# RADIO.net
KiCad netlist of a schematic drawn in EAGLE
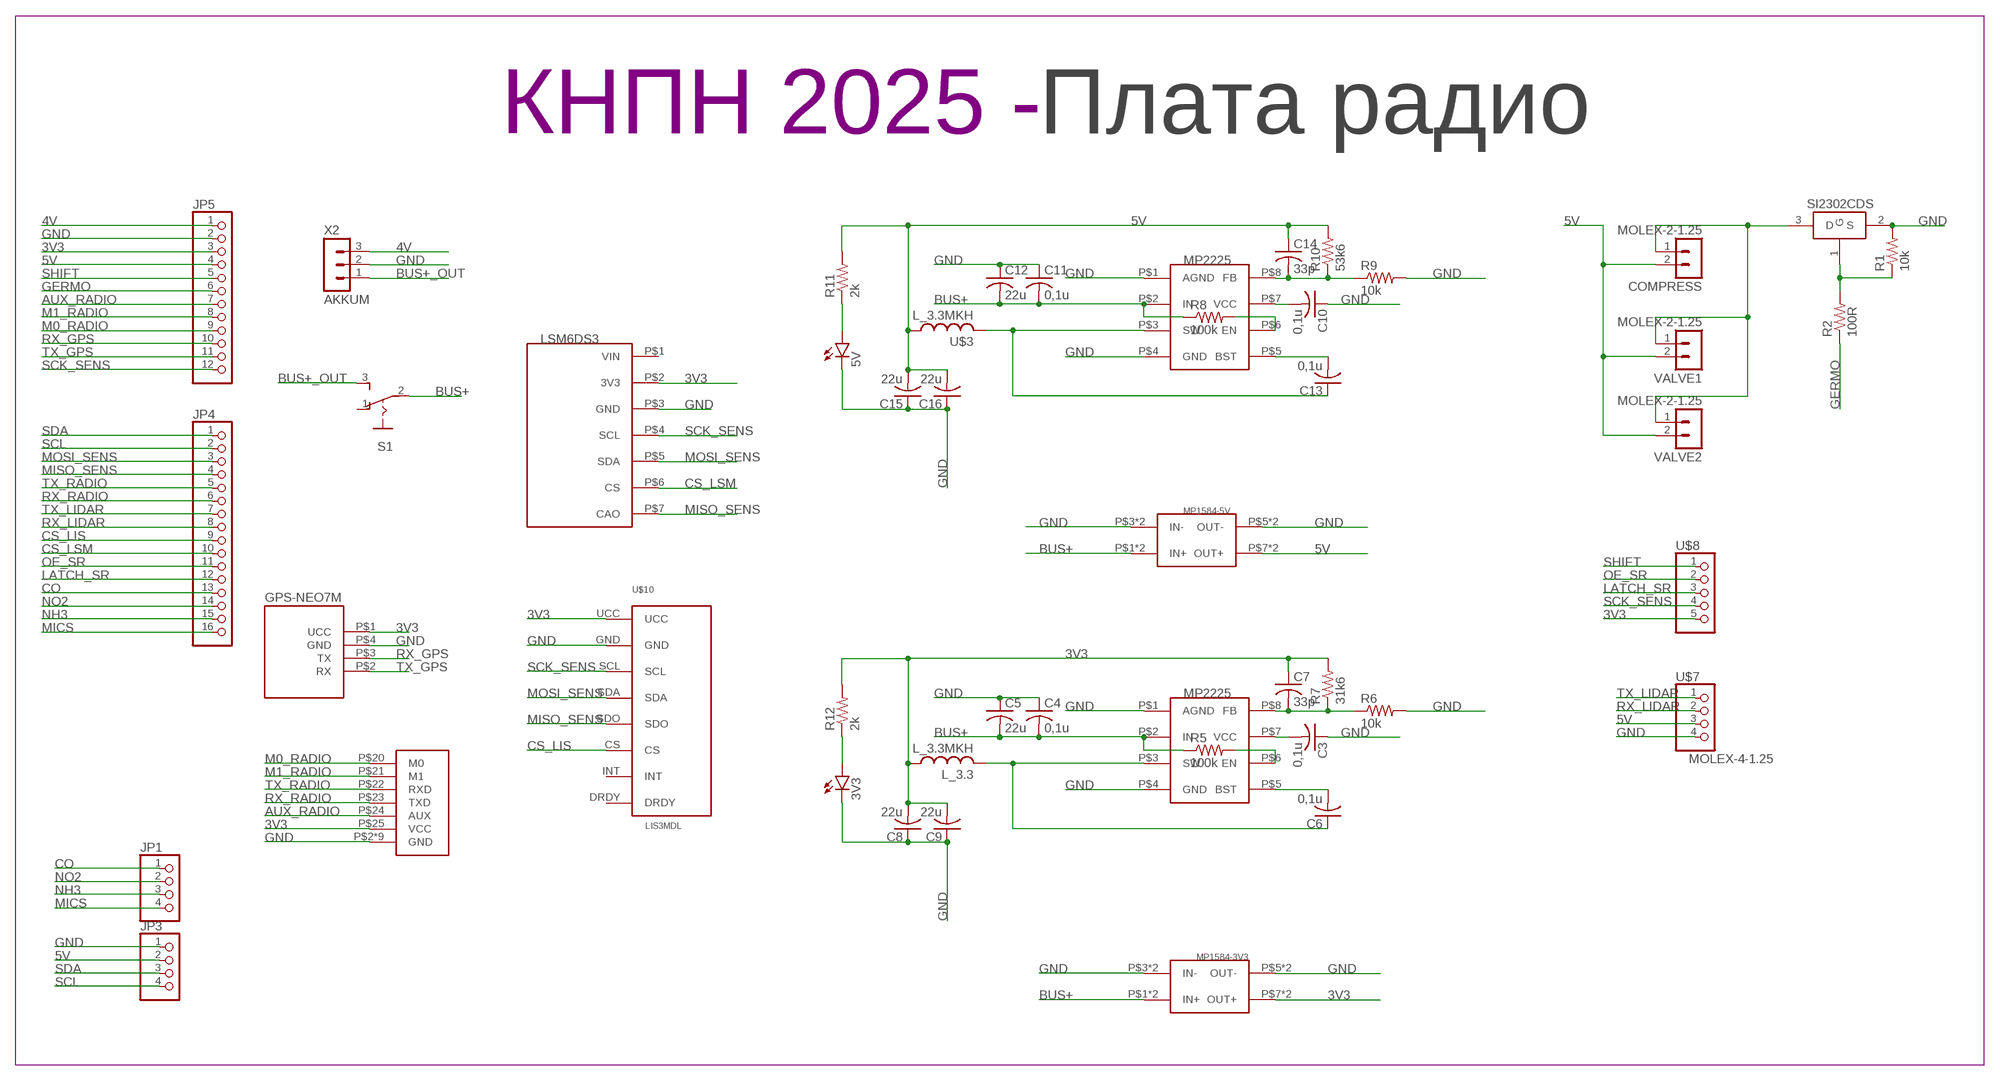
[diagram p0: schematic, sheet 1]

(export (version "E")
  (design (tool "Eeschema 10.0.6"))
  (components
    (comp (ref "3V3")
      (value "LEDCHIP-LED0603")
      (footprint "eagle-import:CHIP-LED0603")
      (libsource (lib "eagle-import") (part "LEDCHIP-LED0603"))
    )
    (comp (ref "5V")
      (value "LEDCHIP-LED0603")
      (footprint "eagle-import:CHIP-LED0603")
      (libsource (lib "eagle-import") (part "LEDCHIP-LED0603"))
    )
    (comp (ref "C3")
      (value "0,1u")
      (footprint "eagle-import:C0603")
      (libsource (lib "eagle-import") (part "C-USC0603"))
    )
    (comp (ref "C4")
      (value "0,1u")
      (footprint "eagle-import:C1206")
      (libsource (lib "eagle-import") (part "C-USC1206"))
    )
    (comp (ref "C5")
      (value "22u")
      (footprint "eagle-import:C0603")
      (libsource (lib "eagle-import") (part "C-USC0603"))
    )
    (comp (ref "C6")
      (value "0,1u")
      (footprint "eagle-import:C0603")
      (libsource (lib "eagle-import") (part "C-USC0603"))
    )
    (comp (ref "C7")
      (value "33p")
      (footprint "eagle-import:C0603")
      (libsource (lib "eagle-import") (part "C-USC0603"))
    )
    (comp (ref "C8")
      (value "22u")
      (footprint "eagle-import:C1206")
      (libsource (lib "eagle-import") (part "C-USC1206"))
    )
    (comp (ref "C9")
      (value "22u")
      (footprint "eagle-import:C1206")
      (libsource (lib "eagle-import") (part "C-USC1206"))
    )
    (comp (ref "C10")
      (value "0,1u")
      (footprint "eagle-import:C0603")
      (libsource (lib "eagle-import") (part "C-USC0603"))
    )
    (comp (ref "C11")
      (value "0,1u")
      (footprint "eagle-import:C1206")
      (libsource (lib "eagle-import") (part "C-USC1206"))
    )
    (comp (ref "C12")
      (value "22u")
      (footprint "eagle-import:C0603")
      (libsource (lib "eagle-import") (part "C-USC0603"))
    )
    (comp (ref "C13")
      (value "0,1u")
      (footprint "eagle-import:C0603")
      (libsource (lib "eagle-import") (part "C-USC0603"))
    )
    (comp (ref "C14")
      (value "33p")
      (footprint "eagle-import:C0603")
      (libsource (lib "eagle-import") (part "C-USC0603"))
    )
    (comp (ref "C15")
      (value "22u")
      (footprint "eagle-import:C1206")
      (libsource (lib "eagle-import") (part "C-USC1206"))
    )
    (comp (ref "C16")
      (value "22u")
      (footprint "eagle-import:C1206")
      (libsource (lib "eagle-import") (part "C-USC1206"))
    )
    (comp (ref "COMPRESS")
      (value "MOLEX-2-1.25")
      (footprint "eagle-import:53047-02")
      (libsource (lib "eagle-import") (part "MOLEX-2-1.25"))
    )
    (comp (ref "GPS-NEO7M")
      (value "GPS-NEO7M")
      (footprint "eagle-import:GPS-NEO7M")
      (libsource (lib "eagle-import") (part "GPS-NEO7M"))
    )
    (comp (ref "JP1")
      (value "PINHD-1X4")
      (footprint "eagle-import:1X04")
      (libsource (lib "eagle-import") (part "PINHD-1X4"))
    )
    (comp (ref "JP3")
      (value "PINHD-1X4")
      (footprint "eagle-import:1X04")
      (libsource (lib "eagle-import") (part "PINHD-1X4"))
    )
    (comp (ref "JP4")
      (value "PINHD-1X16")
      (footprint "eagle-import:1X16")
      (libsource (lib "eagle-import") (part "PINHD-1X16"))
    )
    (comp (ref "JP5")
      (value "PINHD-1X12")
      (footprint "eagle-import:1X12")
      (libsource (lib "eagle-import") (part "PINHD-1X12"))
    )
    (comp (ref "LSM6DS3")
      (value "LSM6DS3")
      (footprint "eagle-import:LSM6DS3_WITHOUT")
      (libsource (lib "eagle-import") (part "LSM6DS3_WITHOUT"))
    )
    (comp (ref "L_3.3")
      (value "L_3.3MKH")
      (footprint "eagle-import:L_SPM5020")
      (libsource (lib "eagle-import") (part "L_3.3MKH_5X5"))
    )
    (comp (ref "MP1584-3V3")
      (value "MP1584-B")
      (footprint "eagle-import:MP1584-B")
      (libsource (lib "eagle-import") (part "MP1584-B"))
    )
    (comp (ref "MP1584-5V")
      (value "MP1584")
      (footprint "eagle-import:MP1584-B")
      (libsource (lib "eagle-import") (part "MP1584-B"))
    )
    (comp (ref "R1")
      (value "10k")
      (footprint "eagle-import:R0603")
      (libsource (lib "eagle-import") (part "R-US_R0603"))
    )
    (comp (ref "R2")
      (value "100R")
      (footprint "eagle-import:R0603")
      (libsource (lib "eagle-import") (part "R-US_R0603"))
    )
    (comp (ref "R5")
      (value "100k")
      (footprint "eagle-import:R0603")
      (libsource (lib "eagle-import") (part "R-US_R0603"))
    )
    (comp (ref "R6")
      (value "10k")
      (footprint "eagle-import:R0603")
      (libsource (lib "eagle-import") (part "R-US_R0603"))
    )
    (comp (ref "R7")
      (value "31k6")
      (footprint "eagle-import:R0603")
      (libsource (lib "eagle-import") (part "R-US_R0603"))
    )
    (comp (ref "R8")
      (value "100k")
      (footprint "eagle-import:R0603")
      (libsource (lib "eagle-import") (part "R-US_R0603"))
    )
    (comp (ref "R9")
      (value "10k")
      (footprint "eagle-import:R0603")
      (libsource (lib "eagle-import") (part "R-US_R0603"))
    )
    (comp (ref "R10")
      (value "53k6")
      (footprint "eagle-import:R0603")
      (libsource (lib "eagle-import") (part "R-US_R0603"))
    )
    (comp (ref "R11")
      (value "2k")
      (footprint "eagle-import:R0603")
      (libsource (lib "eagle-import") (part "R-US_R0603"))
    )
    (comp (ref "R12")
      (value "2k")
      (footprint "eagle-import:R0603")
      (libsource (lib "eagle-import") (part "R-US_R0603"))
    )
    (comp (ref "RADIO")
      (value "E220-400T22S")
      (footprint "eagle-import:E220-400T22S")
      (libsource (lib "eagle-import") (part "E220-400T22S"))
    )
    (comp (ref "S1")
      (value "UNICS-SWITCHSS_12D11")
      (footprint "eagle-import:SS_12D11")
      (libsource (lib "eagle-import") (part "UNICS-SWITCHSS_12D11"))
    )
    (comp (ref "SI2302CDS")
      (value "SI2302CDS")
      (footprint "eagle-import:SOT23-3")
      (libsource (lib "eagle-import") (part "SI2302CDS"))
    )
    (comp (ref "U$1")
      (value "Плата радио")
      (footprint "eagle-import:LOGO")
      (libsource (lib "eagle-import") (part "LOGOPCB-{dblquote}{dblquote}"))
    )
    (comp (ref "U$2")
      (value "MP2225")
      (footprint "eagle-import:TSOT23-8")
      (libsource (lib "eagle-import") (part "MP2225"))
    )
    (comp (ref "U$3")
      (value "L_3.3MKH")
      (footprint "eagle-import:L_SPM5020")
      (libsource (lib "eagle-import") (part "L_3.3MKH_5X5"))
    )
    (comp (ref "U$5")
      (value "MP2225")
      (footprint "eagle-import:TSOT23-8")
      (libsource (lib "eagle-import") (part "MP2225"))
    )
    (comp (ref "U$7")
      (value "MOLEX-4-1.25")
      (footprint "eagle-import:53047-04")
      (libsource (lib "eagle-import") (part "MOLEX-4-1.25"))
    )
    (comp (ref "U$8")
      (value "MOLEX-5-1.25")
      (footprint "eagle-import:53047-05")
      (libsource (lib "eagle-import") (part "MOLEX-5-1.25"))
    )
    (comp (ref "U$10")
      (value "LIS3MDL")
      (footprint "eagle-import:LIS3MDL")
      (libsource (lib "eagle-import") (part "LIS3MDL"))
    )
    (comp (ref "VALVE1")
      (value "MOLEX-2-1.25")
      (footprint "eagle-import:53047-02")
      (libsource (lib "eagle-import") (part "MOLEX-2-1.25"))
    )
    (comp (ref "VALVE2")
      (value "MOLEX-2-1.25")
      (footprint "eagle-import:53047-02")
      (libsource (lib "eagle-import") (part "MOLEX-2-1.25"))
    )
    (comp (ref "X2")
      (value "AKKUM")
      (footprint "eagle-import:JST-3-2.5")
      (libsource (lib "eagle-import") (part "JST-3-2.5"))
    )
  )
  (nets
    (net (code "1") (name "/3V3") (class "Default")
      (node (ref "C7") (pin "1") (pinfunction "1_1") (pintype "passive"))
      (node (ref "C8") (pin "2") (pinfunction "2_2") (pintype "passive"))
      (node (ref "C9") (pin "2") (pinfunction "2_2") (pintype "passive"))
      (node (ref "GPS-NEO7M") (pin "P$1") (pinfunction "UCC_P$1") (pintype "bidirectional"))
      (node (ref "JP5") (pin "3") (pinfunction "3_3") (pintype "passive"))
      (node (ref "LSM6DS3") (pin "P$2") (pinfunction "3V3_P$2") (pintype "bidirectional"))
      (node (ref "L_3.3") (pin "P$1") (pinfunction "1_P$1") (pintype "passive"))
      (node (ref "MP1584-3V3") (pin "P$7") (pinfunction "OUT+_P$7") (pintype "bidirectional"))
      (node (ref "MP1584-3V3") (pin "P$8") (pinfunction "OUT+_P$8") (pintype "bidirectional"))
      (node (ref "R12") (pin "2") (pinfunction "2_2") (pintype "passive"))
      (node (ref "R7") (pin "2") (pinfunction "2_2") (pintype "passive"))
      (node (ref "RADIO") (pin "P$25") (pinfunction "VCC_P$25") (pintype "bidirectional"))
      (node (ref "U$10") (pin "UCC") (pinfunction "UCC_UCC") (pintype "bidirectional"))
      (node (ref "U$8") (pin "5") (pinfunction "5_5") (pintype "passive"))
    )
    (net (code "2") (name "/4V") (class "Default")
      (node (ref "JP5") (pin "1") (pinfunction "1_1") (pintype "passive"))
      (node (ref "X2") (pin "3") (pinfunction "3_3") (pintype "passive"))
    )
    (net (code "3") (name "/5V") (class "Default")
      (node (ref "C14") (pin "1") (pinfunction "1_1") (pintype "passive"))
      (node (ref "C15") (pin "2") (pinfunction "2_2") (pintype "passive"))
      (node (ref "C16") (pin "2") (pinfunction "2_2") (pintype "passive"))
      (node (ref "COMPRESS") (pin "2") (pinfunction "2_2") (pintype "passive"))
      (node (ref "JP3") (pin "2") (pinfunction "2_2") (pintype "passive"))
      (node (ref "JP5") (pin "4") (pinfunction "4_4") (pintype "passive"))
      (node (ref "MP1584-5V") (pin "P$7") (pinfunction "OUT+_P$7") (pintype "bidirectional"))
      (node (ref "MP1584-5V") (pin "P$8") (pinfunction "OUT+_P$8") (pintype "bidirectional"))
      (node (ref "R10") (pin "2") (pinfunction "2_2") (pintype "passive"))
      (node (ref "R11") (pin "2") (pinfunction "2_2") (pintype "passive"))
      (node (ref "U$3") (pin "P$1") (pinfunction "1_P$1") (pintype "passive"))
      (node (ref "U$7") (pin "3") (pinfunction "3_3") (pintype "passive"))
      (node (ref "VALVE1") (pin "2") (pinfunction "2_2") (pintype "passive"))
      (node (ref "VALVE2") (pin "2") (pinfunction "2_2") (pintype "passive"))
    )
    (net (code "4") (name "/AUX_RADIO") (class "Default")
      (node (ref "JP5") (pin "7") (pinfunction "7_7") (pintype "passive"))
      (node (ref "RADIO") (pin "P$24") (pinfunction "AUX_P$24") (pintype "bidirectional"))
    )
    (net (code "5") (name "/BUS+") (class "Default")
      (node (ref "C11") (pin "2") (pinfunction "2_2") (pintype "passive"))
      (node (ref "C12") (pin "2") (pinfunction "2_2") (pintype "passive"))
      (node (ref "C4") (pin "2") (pinfunction "2_2") (pintype "passive"))
      (node (ref "C5") (pin "2") (pinfunction "2_2") (pintype "passive"))
      (node (ref "MP1584-3V3") (pin "P$1") (pinfunction "IN+_P$1") (pintype "bidirectional"))
      (node (ref "MP1584-3V3") (pin "P$2") (pinfunction "IN+_P$2") (pintype "bidirectional"))
      (node (ref "MP1584-5V") (pin "P$1") (pinfunction "IN+_P$1") (pintype "bidirectional"))
      (node (ref "MP1584-5V") (pin "P$2") (pinfunction "IN+_P$2") (pintype "bidirectional"))
      (node (ref "R5") (pin "1") (pinfunction "1_1") (pintype "passive"))
      (node (ref "R8") (pin "1") (pinfunction "1_1") (pintype "passive"))
      (node (ref "S1") (pin "2") (pinfunction "P_2") (pintype "passive"))
      (node (ref "U$2") (pin "P$2") (pinfunction "IN_P$2") (pintype "bidirectional"))
      (node (ref "U$5") (pin "P$2") (pinfunction "IN_P$2") (pintype "bidirectional"))
    )
    (net (code "6") (name "/BUS+_OUT") (class "Default")
      (node (ref "S1") (pin "3") (pinfunction "S_3") (pintype "passive"))
      (node (ref "X2") (pin "1") (pinfunction "1_1") (pintype "passive"))
    )
    (net (code "7") (name "/CO") (class "Default")
      (node (ref "JP1") (pin "1") (pinfunction "1_1") (pintype "passive"))
      (node (ref "JP4") (pin "13") (pinfunction "13_13") (pintype "passive"))
    )
    (net (code "8") (name "/CS_LIS") (class "Default")
      (node (ref "JP4") (pin "9") (pinfunction "9_9") (pintype "passive"))
      (node (ref "U$10") (pin "CS") (pinfunction "CS_CS") (pintype "bidirectional"))
    )
    (net (code "9") (name "/CS_LSM") (class "Default")
      (node (ref "JP4") (pin "10") (pinfunction "10_10") (pintype "passive"))
      (node (ref "LSM6DS3") (pin "P$6") (pinfunction "CS_P$6") (pintype "bidirectional"))
    )
    (net (code "10") (name "/GERMO") (class "Default")
      (node (ref "JP5") (pin "6") (pinfunction "6_6") (pintype "passive"))
      (node (ref "R2") (pin "1") (pinfunction "1_1") (pintype "passive"))
    )
    (net (code "11") (name "/GND") (class "Default")
      (node (ref "3V3") (pin "C") (pinfunction "C_C") (pintype "passive"))
      (node (ref "5V") (pin "C") (pinfunction "C_C") (pintype "passive"))
      (node (ref "C10") (pin "1") (pinfunction "1_1") (pintype "passive"))
      (node (ref "C11") (pin "1") (pinfunction "1_1") (pintype "passive"))
      (node (ref "C12") (pin "1") (pinfunction "1_1") (pintype "passive"))
      (node (ref "C15") (pin "1") (pinfunction "1_1") (pintype "passive"))
      (node (ref "C16") (pin "1") (pinfunction "1_1") (pintype "passive"))
      (node (ref "C3") (pin "1") (pinfunction "1_1") (pintype "passive"))
      (node (ref "C4") (pin "1") (pinfunction "1_1") (pintype "passive"))
      (node (ref "C5") (pin "1") (pinfunction "1_1") (pintype "passive"))
      (node (ref "C8") (pin "1") (pinfunction "1_1") (pintype "passive"))
      (node (ref "C9") (pin "1") (pinfunction "1_1") (pintype "passive"))
      (node (ref "GPS-NEO7M") (pin "P$4") (pinfunction "GND_P$4") (pintype "bidirectional"))
      (node (ref "JP3") (pin "1") (pinfunction "1_1") (pintype "passive"))
      (node (ref "JP5") (pin "2") (pinfunction "2_2") (pintype "passive"))
      (node (ref "LSM6DS3") (pin "P$3") (pinfunction "GND_P$3") (pintype "bidirectional"))
      (node (ref "MP1584-3V3") (pin "P$3") (pinfunction "IN-_P$3") (pintype "bidirectional"))
      (node (ref "MP1584-3V3") (pin "P$4") (pinfunction "IN-_P$4") (pintype "bidirectional"))
      (node (ref "MP1584-3V3") (pin "P$5") (pinfunction "OUT-_P$5") (pintype "bidirectional"))
      (node (ref "MP1584-3V3") (pin "P$6") (pinfunction "OUT-_P$6") (pintype "bidirectional"))
      (node (ref "MP1584-5V") (pin "P$3") (pinfunction "IN-_P$3") (pintype "bidirectional"))
      (node (ref "MP1584-5V") (pin "P$4") (pinfunction "IN-_P$4") (pintype "bidirectional"))
      (node (ref "MP1584-5V") (pin "P$5") (pinfunction "OUT-_P$5") (pintype "bidirectional"))
      (node (ref "MP1584-5V") (pin "P$6") (pinfunction "OUT-_P$6") (pintype "bidirectional"))
      (node (ref "R1") (pin "2") (pinfunction "2_2") (pintype "passive"))
      (node (ref "R6") (pin "2") (pinfunction "2_2") (pintype "passive"))
      (node (ref "R9") (pin "2") (pinfunction "2_2") (pintype "passive"))
      (node (ref "RADIO") (pin "P$11") (pinfunction "GND_P$11") (pintype "bidirectional"))
      (node (ref "RADIO") (pin "P$13") (pinfunction "GND_P$13") (pintype "bidirectional"))
      (node (ref "RADIO") (pin "P$14") (pinfunction "GND_P$14") (pintype "bidirectional"))
      (node (ref "RADIO") (pin "P$15") (pinfunction "GND_P$15") (pintype "bidirectional"))
      (node (ref "RADIO") (pin "P$16") (pinfunction "GND_P$16") (pintype "bidirectional"))
      (node (ref "RADIO") (pin "P$19") (pinfunction "GND_P$19") (pintype "bidirectional"))
      (node (ref "RADIO") (pin "P$2") (pinfunction "GND_P$2") (pintype "bidirectional"))
      (node (ref "RADIO") (pin "P$26") (pinfunction "GND_P$26") (pintype "bidirectional"))
      (node (ref "RADIO") (pin "P$8") (pinfunction "GND_P$8") (pintype "bidirectional"))
      (node (ref "SI2302CDS") (pin "2") (pinfunction "S_2") (pintype "bidirectional"))
      (node (ref "U$10") (pin "GND") (pinfunction "GND_GND") (pintype "bidirectional"))
      (node (ref "U$2") (pin "P$1") (pinfunction "AGND_P$1") (pintype "bidirectional"))
      (node (ref "U$2") (pin "P$4") (pinfunction "GND_P$4") (pintype "bidirectional"))
      (node (ref "U$5") (pin "P$1") (pinfunction "AGND_P$1") (pintype "bidirectional"))
      (node (ref "U$5") (pin "P$4") (pinfunction "GND_P$4") (pintype "bidirectional"))
      (node (ref "U$7") (pin "4") (pinfunction "4_4") (pintype "passive"))
      (node (ref "X2") (pin "2") (pinfunction "2_2") (pintype "passive"))
    )
    (net (code "12") (name "/LATCH_SR") (class "Default")
      (node (ref "JP4") (pin "12") (pinfunction "12_12") (pintype "passive"))
      (node (ref "U$8") (pin "3") (pinfunction "3_3") (pintype "passive"))
    )
    (net (code "13") (name "/M0_RADIO") (class "Default")
      (node (ref "JP5") (pin "9") (pinfunction "9_9") (pintype "passive"))
      (node (ref "RADIO") (pin "P$20") (pinfunction "M0_P$20") (pintype "bidirectional"))
    )
    (net (code "14") (name "/M1_RADIO") (class "Default")
      (node (ref "JP5") (pin "8") (pinfunction "8_8") (pintype "passive"))
      (node (ref "RADIO") (pin "P$21") (pinfunction "M1_P$21") (pintype "bidirectional"))
    )
    (net (code "15") (name "/MICS") (class "Default")
      (node (ref "JP1") (pin "4") (pinfunction "4_4") (pintype "passive"))
      (node (ref "JP4") (pin "16") (pinfunction "16_16") (pintype "passive"))
    )
    (net (code "16") (name "/MISO_SENS") (class "Default")
      (node (ref "JP4") (pin "4") (pinfunction "4_4") (pintype "passive"))
      (node (ref "LSM6DS3") (pin "P$7") (pinfunction "CAO_P$7") (pintype "bidirectional"))
      (node (ref "U$10") (pin "SDO") (pinfunction "SDO_SDO") (pintype "bidirectional"))
    )
    (net (code "17") (name "/MOSI_SENS") (class "Default")
      (node (ref "JP4") (pin "3") (pinfunction "3_3") (pintype "passive"))
      (node (ref "LSM6DS3") (pin "P$5") (pinfunction "SDA_P$5") (pintype "bidirectional"))
      (node (ref "U$10") (pin "SDA") (pinfunction "SDA_SDA") (pintype "bidirectional"))
    )
    (net (code "18") (name "/NH3") (class "Default")
      (node (ref "JP1") (pin "3") (pinfunction "3_3") (pintype "passive"))
      (node (ref "JP4") (pin "15") (pinfunction "15_15") (pintype "passive"))
    )
    (net (code "19") (name "/NO2") (class "Default")
      (node (ref "JP1") (pin "2") (pinfunction "2_2") (pintype "passive"))
      (node (ref "JP4") (pin "14") (pinfunction "14_14") (pintype "passive"))
    )
    (net (code "20") (name "/OE_SR") (class "Default")
      (node (ref "JP4") (pin "11") (pinfunction "11_11") (pintype "passive"))
      (node (ref "U$8") (pin "2") (pinfunction "2_2") (pintype "passive"))
    )
    (net (code "21") (name "/RX_GPS") (class "Default")
      (node (ref "GPS-NEO7M") (pin "P$3") (pinfunction "TX_P$3") (pintype "bidirectional"))
      (node (ref "JP5") (pin "10") (pinfunction "10_10") (pintype "passive"))
    )
    (net (code "22") (name "/RX_LIDAR") (class "Default")
      (node (ref "JP4") (pin "8") (pinfunction "8_8") (pintype "passive"))
      (node (ref "U$7") (pin "2") (pinfunction "2_2") (pintype "passive"))
    )
    (net (code "23") (name "/RX_RADIO") (class "Default")
      (node (ref "JP4") (pin "6") (pinfunction "6_6") (pintype "passive"))
      (node (ref "RADIO") (pin "P$23") (pinfunction "TXD_P$23") (pintype "bidirectional"))
    )
    (net (code "24") (name "/SCK_SENS") (class "Default")
      (node (ref "JP5") (pin "12") (pinfunction "12_12") (pintype "passive"))
      (node (ref "LSM6DS3") (pin "P$4") (pinfunction "SCL_P$4") (pintype "bidirectional"))
      (node (ref "U$10") (pin "SCL") (pinfunction "SCL_SCL") (pintype "bidirectional"))
      (node (ref "U$8") (pin "4") (pinfunction "4_4") (pintype "passive"))
    )
    (net (code "25") (name "/SCL") (class "Default")
      (node (ref "JP3") (pin "4") (pinfunction "4_4") (pintype "passive"))
      (node (ref "JP4") (pin "2") (pinfunction "2_2") (pintype "passive"))
    )
    (net (code "26") (name "/SDA") (class "Default")
      (node (ref "JP3") (pin "3") (pinfunction "3_3") (pintype "passive"))
      (node (ref "JP4") (pin "1") (pinfunction "1_1") (pintype "passive"))
    )
    (net (code "27") (name "/SHIFT") (class "Default")
      (node (ref "JP5") (pin "5") (pinfunction "5_5") (pintype "passive"))
      (node (ref "U$8") (pin "1") (pinfunction "1_1") (pintype "passive"))
    )
    (net (code "28") (name "/TX_GPS") (class "Default")
      (node (ref "GPS-NEO7M") (pin "P$2") (pinfunction "RX_P$2") (pintype "bidirectional"))
      (node (ref "JP5") (pin "11") (pinfunction "11_11") (pintype "passive"))
    )
    (net (code "29") (name "/TX_LIDAR") (class "Default")
      (node (ref "JP4") (pin "7") (pinfunction "7_7") (pintype "passive"))
      (node (ref "U$7") (pin "1") (pinfunction "1_1") (pintype "passive"))
    )
    (net (code "30") (name "/TX_RADIO") (class "Default")
      (node (ref "JP4") (pin "5") (pinfunction "5_5") (pintype "passive"))
      (node (ref "RADIO") (pin "P$22") (pinfunction "RXD_P$22") (pintype "bidirectional"))
    )
    (net (code "31") (name "Net-(3V3-PadA)") (class "Default")
      (node (ref "3V3") (pin "A") (pinfunction "A_A") (pintype "passive"))
      (node (ref "R12") (pin "1") (pinfunction "1_1") (pintype "passive"))
    )
    (net (code "32") (name "Net-(5V-PadA)") (class "Default")
      (node (ref "5V") (pin "A") (pinfunction "A_A") (pintype "passive"))
      (node (ref "R11") (pin "1") (pinfunction "1_1") (pintype "passive"))
    )
    (net (code "33") (name "Net-(L_3.3-2)") (class "Default")
      (node (ref "C6") (pin "1") (pinfunction "1_1") (pintype "passive"))
      (node (ref "L_3.3") (pin "P$2") (pinfunction "2_P$2") (pintype "passive"))
      (node (ref "U$2") (pin "P$3") (pinfunction "SW_P$3") (pintype "bidirectional"))
    )
    (net (code "34") (name "Net-(SI2302CDS-D)") (class "Default")
      (node (ref "COMPRESS") (pin "1") (pinfunction "1_1") (pintype "passive"))
      (node (ref "SI2302CDS") (pin "3") (pinfunction "D_3") (pintype "bidirectional"))
      (node (ref "VALVE1") (pin "1") (pinfunction "1_1") (pintype "passive"))
      (node (ref "VALVE2") (pin "1") (pinfunction "1_1") (pintype "passive"))
    )
    (net (code "35") (name "Net-(SI2302CDS-G)") (class "Default")
      (node (ref "R1") (pin "1") (pinfunction "1_1") (pintype "passive"))
      (node (ref "R2") (pin "2") (pinfunction "2_2") (pintype "passive"))
      (node (ref "SI2302CDS") (pin "1") (pinfunction "G_1") (pintype "bidirectional"))
    )
    (net (code "36") (name "Net-(U$2-BST)") (class "Default")
      (node (ref "C6") (pin "2") (pinfunction "2_2") (pintype "passive"))
      (node (ref "U$2") (pin "P$5") (pinfunction "BST_P$5") (pintype "bidirectional"))
    )
    (net (code "37") (name "Net-(U$2-EN)") (class "Default")
      (node (ref "R5") (pin "2") (pinfunction "2_2") (pintype "passive"))
      (node (ref "U$2") (pin "P$6") (pinfunction "EN_P$6") (pintype "bidirectional"))
    )
    (net (code "38") (name "Net-(U$2-FB)") (class "Default")
      (node (ref "C7") (pin "2") (pinfunction "2_2") (pintype "passive"))
      (node (ref "R6") (pin "1") (pinfunction "1_1") (pintype "passive"))
      (node (ref "R7") (pin "1") (pinfunction "1_1") (pintype "passive"))
      (node (ref "U$2") (pin "P$8") (pinfunction "FB_P$8") (pintype "bidirectional"))
    )
    (net (code "39") (name "Net-(U$2-VCC)") (class "Default")
      (node (ref "C3") (pin "2") (pinfunction "2_2") (pintype "passive"))
      (node (ref "U$2") (pin "P$7") (pinfunction "VCC_P$7") (pintype "bidirectional"))
    )
    (net (code "40") (name "Net-(U$3-2)") (class "Default")
      (node (ref "C13") (pin "1") (pinfunction "1_1") (pintype "passive"))
      (node (ref "U$3") (pin "P$2") (pinfunction "2_P$2") (pintype "passive"))
      (node (ref "U$5") (pin "P$3") (pinfunction "SW_P$3") (pintype "bidirectional"))
    )
    (net (code "41") (name "Net-(U$5-BST)") (class "Default")
      (node (ref "C13") (pin "2") (pinfunction "2_2") (pintype "passive"))
      (node (ref "U$5") (pin "P$5") (pinfunction "BST_P$5") (pintype "bidirectional"))
    )
    (net (code "42") (name "Net-(U$5-EN)") (class "Default")
      (node (ref "R8") (pin "2") (pinfunction "2_2") (pintype "passive"))
      (node (ref "U$5") (pin "P$6") (pinfunction "EN_P$6") (pintype "bidirectional"))
    )
    (net (code "43") (name "Net-(U$5-FB)") (class "Default")
      (node (ref "C14") (pin "2") (pinfunction "2_2") (pintype "passive"))
      (node (ref "R10") (pin "1") (pinfunction "1_1") (pintype "passive"))
      (node (ref "R9") (pin "1") (pinfunction "1_1") (pintype "passive"))
      (node (ref "U$5") (pin "P$8") (pinfunction "FB_P$8") (pintype "bidirectional"))
    )
    (net (code "44") (name "Net-(U$5-VCC)") (class "Default")
      (node (ref "C10") (pin "2") (pinfunction "2_2") (pintype "passive"))
      (node (ref "U$5") (pin "P$7") (pinfunction "VCC_P$7") (pintype "bidirectional"))
    )
    (net (code "45") (name "unconnected-(LSM6DS3-VIN-PadP$1)") (class "Default")
      (node (ref "LSM6DS3") (pin "P$1") (pinfunction "VIN_P$1") (pintype "bidirectional"))
    )
    (net (code "46") (name "unconnected-(S1-O-Pad1)") (class "Default")
      (node (ref "S1") (pin "1") (pinfunction "O_1") (pintype "passive"))
    )
    (net (code "47") (name "unconnected-(U$10-PadDRDY)") (class "Default")
      (node (ref "U$10") (pin "DRDY") (pinfunction "DRDY_DRDY") (pintype "bidirectional"))
    )
    (net (code "48") (name "unconnected-(U$10-PadINT)") (class "Default")
      (node (ref "U$10") (pin "INT") (pinfunction "INT_INT") (pintype "bidirectional"))
    )
  )
)
